# STM32WB55CGU6.net
KiCad netlist of a schematic drawn in Altium Designer
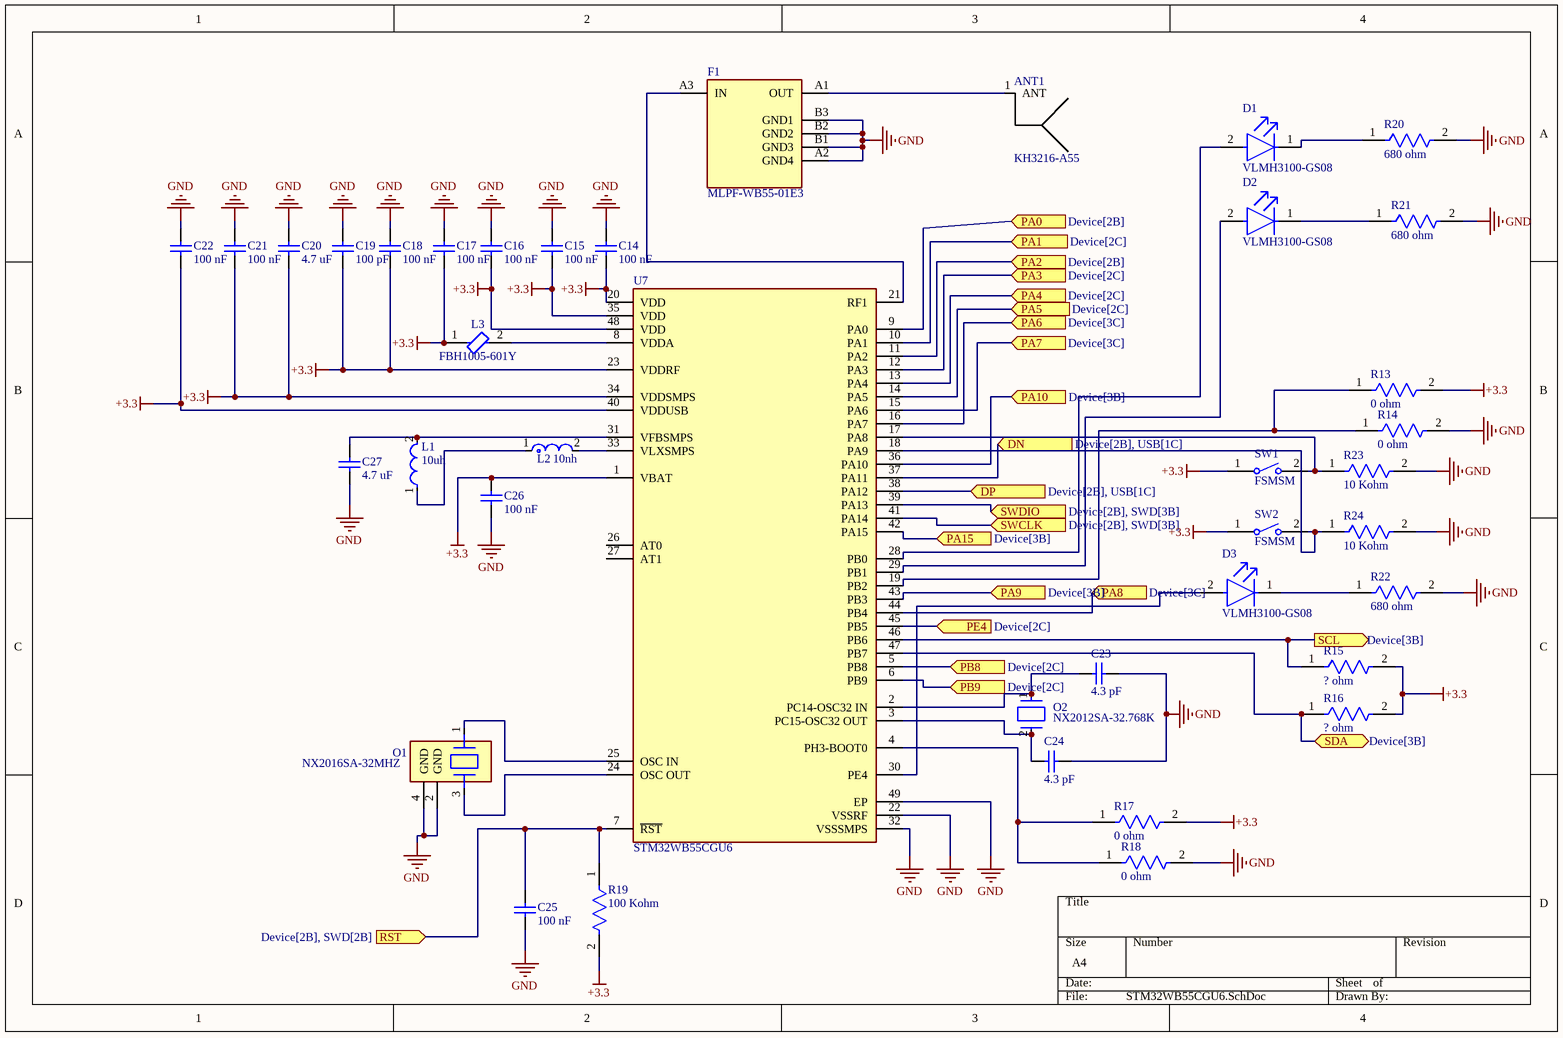
[diagram p0: STM32WB55CGU6.SchDoc]

(export (version "E")
  (design (tool "Eeschema 10.0.6"))
  (components
    (comp (ref "ANT1")
      (value "KH3216-A55")
      (footprint "KH3216-A55")
      (libsource (lib "ANT") (part "KH3216-A55"))
    )
    (comp (ref "C14")
      (value "100 nF")
      (footprint "CAPC1005X55X25NL05T10")
      (fields (field (name "MANUFACTURER") "Murata") (field (name "PART NUMBER") "GRM155F50J684ZE01D"))
      (libsource (lib "Altium Content Vault") (part "CAP"))
    )
    (comp (ref "C15")
      (value "100 nF")
      (footprint "CAPC1005X55X25NL05T10")
      (fields (field (name "MANUFACTURER") "Murata") (field (name "PART NUMBER") "GRM155F50J684ZE01D"))
      (libsource (lib "Altium Content Vault") (part "CAP"))
    )
    (comp (ref "C16")
      (value "100 nF")
      (footprint "CAPC1005X55X25NL05T10")
      (fields (field (name "MANUFACTURER") "Murata") (field (name "PART NUMBER") "GRM155F50J684ZE01D"))
      (libsource (lib "Altium Content Vault") (part "CAP"))
    )
    (comp (ref "C17")
      (value "100 nF")
      (footprint "CAPC1005X55X25NL05T10")
      (fields (field (name "MANUFACTURER") "Murata") (field (name "PART NUMBER") "GRM155F50J684ZE01D"))
      (libsource (lib "Altium Content Vault") (part "CAP"))
    )
    (comp (ref "C18")
      (value "100 nF")
      (footprint "CAPC1005X55X25NL05T10")
      (fields (field (name "MANUFACTURER") "Murata") (field (name "PART NUMBER") "GRM155F50J684ZE01D"))
      (libsource (lib "Altium Content Vault") (part "CAP"))
    )
    (comp (ref "C19")
      (value "100 pF")
      (footprint "CAPC1005X55X25NL05T10")
      (fields (field (name "MANUFACTURER") "Murata") (field (name "PART NUMBER") "GRM155F50J684ZE01D"))
      (libsource (lib "Altium Content Vault") (part "CAP"))
    )
    (comp (ref "C20")
      (value "4.7 uF")
      (footprint "CAPC1005X55X25NL05T10")
      (fields (field (name "MANUFACTURER") "Murata") (field (name "PART NUMBER") "GRM155F50J684ZE01D"))
      (libsource (lib "Altium Content Vault") (part "CAP"))
    )
    (comp (ref "C21")
      (value "100 nF")
      (footprint "CAPC1005X55X25NL05T10")
      (fields (field (name "MANUFACTURER") "Murata") (field (name "PART NUMBER") "GRM155F50J684ZE01D"))
      (libsource (lib "Altium Content Vault") (part "CAP"))
    )
    (comp (ref "C22")
      (value "100 nF")
      (footprint "CAPC1005X55X25NL05T10")
      (fields (field (name "MANUFACTURER") "Murata") (field (name "PART NUMBER") "GRM155F50J684ZE01D"))
      (libsource (lib "Altium Content Vault") (part "CAP"))
    )
    (comp (ref "C23")
      (value "4.3 pF")
      (footprint "CAPC1005X55X25NL05T10")
      (fields (field (name "MANUFACTURER") "Murata") (field (name "PART NUMBER") "GRM155F50J684ZE01D"))
      (libsource (lib "Altium Content Vault") (part "CAP"))
    )
    (comp (ref "C24")
      (value "4.3 pF")
      (footprint "CAPC1005X55X25NL05T10")
      (fields (field (name "MANUFACTURER") "Murata") (field (name "PART NUMBER") "GRM155F50J684ZE01D"))
      (libsource (lib "Altium Content Vault") (part "CAP"))
    )
    (comp (ref "C25")
      (value "100 nF")
      (footprint "CAPC1005X55X25NL05T10")
      (fields (field (name "MANUFACTURER") "Murata") (field (name "PART NUMBER") "GRM155F50J684ZE01D"))
      (libsource (lib "Altium Content Vault") (part "CAP"))
    )
    (comp (ref "C26")
      (value "100 nF")
      (footprint "CAPC1005X55X25NL05T10")
      (fields (field (name "MANUFACTURER") "Murata") (field (name "PART NUMBER") "GRM155F50J684ZE01D"))
      (libsource (lib "Altium Content Vault") (part "CAP"))
    )
    (comp (ref "C27")
      (value "4.7 uF")
      (footprint "CAPC1005X55X25NL05T10")
      (fields (field (name "MANUFACTURER") "Murata") (field (name "PART NUMBER") "GRM155F50J684ZE01D"))
      (libsource (lib "Altium Content Vault") (part "CAP"))
    )
    (comp (ref "D1")
      (value "VLMH3100-GS08")
      (footprint "FP-6_541-5067_01-4-MFG")
      (description "LED AMBER CLEAR 2PLCC SMD")
      (fields
        (field (name "MANUFACTURER") "Vishay")
        (field (name "OCTOPART") "https://octopart.com/vlmh3100-gs08-vishay-10477172")
      )
      (libsource (lib "Altium Content Vault") (part "f19a1b30ec2e0e83542a893ae8c56fc"))
    )
    (comp (ref "D2")
      (value "VLMH3100-GS08")
      (footprint "FP-6_541-5067_01-4-MFG")
      (description "LED AMBER CLEAR 2PLCC SMD")
      (fields
        (field (name "MANUFACTURER") "Vishay")
        (field (name "OCTOPART") "https://octopart.com/vlmh3100-gs08-vishay-10477172")
      )
      (libsource (lib "Altium Content Vault") (part "f19a1b30ec2e0e83542a893ae8c56fc"))
    )
    (comp (ref "D3")
      (value "VLMH3100-GS08")
      (footprint "FP-6_541-5067_01-4-MFG")
      (description "LED AMBER CLEAR 2PLCC SMD")
      (fields
        (field (name "MANUFACTURER") "Vishay")
        (field (name "OCTOPART") "https://octopart.com/vlmh3100-gs08-vishay-10477172")
      )
      (libsource (lib "Altium Content Vault") (part "f19a1b30ec2e0e83542a893ae8c56fc"))
    )
    (comp (ref "F1")
      (value "MLPF-WB55-01E3")
      (footprint "FP-MLPF-WB55-01E3-MFG")
      (description "RF FILTER LOW PASS 2.45GHZ 6SMD")
      (libsource (lib "Altium Content Vault") (part "51e28da9fe7b2e4e5e03ac85244eada"))
    )
    (comp (ref "L1")
      (value "10uh")
      (footprint "FP-LQM21FN_70-MFG")
      (description "FIXED IND 10UH 100MA 780MOHM SMD")
      (fields (field (name "TOLERANCE") "20%"))
      (libsource (lib "Altium Content Vault") (part "725321dda6339637d4d059423bc1c3c"))
    )
    (comp (ref "L2")
      (value "10nh")
      (footprint "FP-LQG15WH_02-MFG")
      (description "Multilayer type Inductor for Automotive 10nH ±5% 0.19Ω 500mA 0402")
      (fields (field (name "TOLERANCE") "5%"))
      (libsource (lib "Altium Content Vault") (part "4cc4b267dca4c8e51f7102f422741d8"))
    )
    (comp (ref "L3")
      (value "FBH1005-601Y")
      (footprint "FP-BLM15-0_05-MFG")
      (description "Chip Ferrite Bead, 0402, 600Ω @ 100MHz, 0.52Ω, 25%, 300mA")
      (fields (field (name "TOLERANCE") "25%"))
      (libsource (lib "Altium Content Vault") (part "5f30dd21d616792df468990f7003faa"))
    )
    (comp (ref "O1")
      (value "NX2016SA-32MHZ")
      (footprint "FP-NX2016SA-MFG")
      (description "CRYSTAL 32.0000MHZ 8PF SMD")
      (libsource (lib "Altium Content Vault") (part "0d11ad3ca7be055efd3b4f344707230"))
    )
    (comp (ref "O2")
      (value "NX2012SA-32.768K")
      (footprint "FP-NX2012SA-MFG")
      (description "CRYSTAL 32.7680KHZ 12.5PF SMD")
      (libsource (lib "Altium Content Vault") (part "c23a69dc6c9e2f18f2079038eb95dd1"))
    )
    (comp (ref "R13")
      (value "0 ohm")
      (footprint "FP-RC1005-IPC_C")
      (description "Res Thick Film 0402 1.87kΩ 1% 0.063W ±100ppm/°C Molded SMD T/R")
      (fields (field (name "TOLERANCE") "1%"))
      (libsource (lib "Altium Content Vault") (part "1029c3af85768c4190bb7ad29bc67b5"))
    )
    (comp (ref "R14")
      (value "0 ohm")
      (footprint "FP-RC1005-IPC_C")
      (description "Res Thick Film 0402 1.87kΩ 1% 0.063W ±100ppm/°C Molded SMD T/R")
      (fields (field (name "TOLERANCE") "1%"))
      (libsource (lib "Altium Content Vault") (part "1029c3af85768c4190bb7ad29bc67b5"))
    )
    (comp (ref "R15")
      (value "? ohm")
      (footprint "FP-RC1005-IPC_C")
      (description "Res Thick Film 0402 1.87kΩ 1% 0.063W ±100ppm/°C Molded SMD T/R")
      (fields (field (name "TOLERANCE") "1%"))
      (libsource (lib "Altium Content Vault") (part "1029c3af85768c4190bb7ad29bc67b5"))
    )
    (comp (ref "R16")
      (value "? ohm")
      (footprint "FP-RC1005-IPC_C")
      (description "Res Thick Film 0402 1.87kΩ 1% 0.063W ±100ppm/°C Molded SMD T/R")
      (fields (field (name "TOLERANCE") "1%"))
      (libsource (lib "Altium Content Vault") (part "1029c3af85768c4190bb7ad29bc67b5"))
    )
    (comp (ref "R17")
      (value "0 ohm")
      (footprint "FP-RC1005-IPC_C")
      (description "Res Thick Film 0402 1.87kΩ 1% 0.063W ±100ppm/°C Molded SMD T/R")
      (fields (field (name "TOLERANCE") "1%"))
      (libsource (lib "Altium Content Vault") (part "1029c3af85768c4190bb7ad29bc67b5"))
    )
    (comp (ref "R18")
      (value "0 ohm")
      (footprint "FP-RC1005-IPC_C")
      (description "Res Thick Film 0402 1.87kΩ 1% 0.063W ±100ppm/°C Molded SMD T/R")
      (fields (field (name "TOLERANCE") "1%"))
      (libsource (lib "Altium Content Vault") (part "1029c3af85768c4190bb7ad29bc67b5"))
    )
    (comp (ref "R19")
      (value "100 Kohm")
      (footprint "FP-RC1005-IPC_C")
      (description "Res Thick Film 0402 1.87kΩ 1% 0.063W ±100ppm/°C Molded SMD T/R")
      (fields (field (name "TOLERANCE") "1%"))
      (libsource (lib "Altium Content Vault") (part "1029c3af85768c4190bb7ad29bc67b5"))
    )
    (comp (ref "R20")
      (value "680 ohm")
      (footprint "FP-RC1005-IPC_C")
      (description "Res Thick Film 0402 1.87kΩ 1% 0.063W ±100ppm/°C Molded SMD T/R")
      (fields (field (name "TOLERANCE") "1%"))
      (libsource (lib "Altium Content Vault") (part "1029c3af85768c4190bb7ad29bc67b5"))
    )
    (comp (ref "R21")
      (value "680 ohm")
      (footprint "FP-RC1005-IPC_C")
      (description "Res Thick Film 0402 1.87kΩ 1% 0.063W ±100ppm/°C Molded SMD T/R")
      (fields (field (name "TOLERANCE") "1%"))
      (libsource (lib "Altium Content Vault") (part "1029c3af85768c4190bb7ad29bc67b5"))
    )
    (comp (ref "R22")
      (value "680 ohm")
      (footprint "FP-RC1005-IPC_C")
      (description "Res Thick Film 0402 1.87kΩ 1% 0.063W ±100ppm/°C Molded SMD T/R")
      (fields (field (name "TOLERANCE") "1%"))
      (libsource (lib "Altium Content Vault") (part "1029c3af85768c4190bb7ad29bc67b5"))
    )
    (comp (ref "R23")
      (value "10 Kohm")
      (footprint "FP-RC1005-IPC_C")
      (description "Res Thick Film 0402 1.87kΩ 1% 0.063W ±100ppm/°C Molded SMD T/R")
      (fields (field (name "TOLERANCE") "1%"))
      (libsource (lib "Altium Content Vault") (part "1029c3af85768c4190bb7ad29bc67b5"))
    )
    (comp (ref "R24")
      (value "10 Kohm")
      (footprint "FP-RC1005-IPC_C")
      (description "Res Thick Film 0402 1.87kΩ 1% 0.063W ±100ppm/°C Molded SMD T/R")
      (fields (field (name "TOLERANCE") "1%"))
      (libsource (lib "Altium Content Vault") (part "1029c3af85768c4190bb7ad29bc67b5"))
    )
    (comp (ref "SW1")
      (value "FSMSM")
      (footprint "TECO-FSMSM-2_V")
      (description "FSMSM Push Button Switch, 50 mA, -35 to 85 degC, 2-Pin SMD, RoHS, Bulk")
      (fields (field (name "MANUFACTURER") "TE Connectivity"))
      (libsource (lib "Altium Content Vault") (part "SW-SPST-2_C"))
    )
    (comp (ref "SW2")
      (value "FSMSM")
      (footprint "TECO-FSMSM-2_V")
      (description "FSMSM Push Button Switch, 50 mA, -35 to 85 degC, 2-Pin SMD, RoHS, Bulk")
      (fields (field (name "MANUFACTURER") "TE Connectivity"))
      (libsource (lib "Altium Content Vault") (part "SW-SPST-2_C"))
    )
    (comp (ref "U7")
      (value "STM32WB55CGU6")
      (footprint "FP-STM32WB55CGU6-MFG")
      (description "ULTRA-LOW-POWER DUAL CORE ARM CO")
      (fields
        (field (name "OCTOPART") "https://octopart.com/stm32wb55cgu6-stmicroelectronics-98750847")
        (field (name "MANUFACTURER") "STMicroelectronics")
      )
      (libsource (lib "Altium Content Vault") (part "9d9ca7f3567da95c474f3f549f05e68"))
    )
  )
  (nets
    (net (code "1") (name "+3.3") (class "Default")
      (node (ref "C14") (pin "1") (pinfunction "1_1") (pintype "passive"))
      (node (ref "C15") (pin "2") (pinfunction "2_2") (pintype "passive"))
      (node (ref "C16") (pin "1") (pinfunction "1_1") (pintype "passive"))
      (node (ref "C17") (pin "2") (pinfunction "2_2") (pintype "passive"))
      (node (ref "C18") (pin "1") (pinfunction "1_1") (pintype "passive"))
      (node (ref "C19") (pin "2") (pinfunction "2_2") (pintype "passive"))
      (node (ref "C20") (pin "2") (pinfunction "2_2") (pintype "passive"))
      (node (ref "C21") (pin "1") (pinfunction "1_1") (pintype "passive"))
      (node (ref "C22") (pin "2") (pinfunction "2_2") (pintype "passive"))
      (node (ref "C26") (pin "2") (pinfunction "2_2") (pintype "passive"))
      (node (ref "L3") (pin "1") (pinfunction "1_1") (pintype "passive"))
      (node (ref "R13") (pin "2") (pinfunction "2_2") (pintype "passive"))
      (node (ref "R15") (pin "2") (pinfunction "2_2") (pintype "passive"))
      (node (ref "R16") (pin "2") (pinfunction "2_2") (pintype "passive"))
      (node (ref "R17") (pin "2") (pinfunction "2_2") (pintype "passive"))
      (node (ref "R19") (pin "2") (pinfunction "2_2") (pintype "passive"))
      (node (ref "SW1") (pin "1") (pinfunction "1_1") (pintype "passive"))
      (node (ref "SW2") (pin "1") (pinfunction "1_1") (pintype "passive"))
      (node (ref "U7") (pin "1") (pinfunction "VBAT_1") (pintype "passive"))
      (node (ref "U7") (pin "20") (pinfunction "VDD_20") (pintype "passive"))
      (node (ref "U7") (pin "23") (pinfunction "VDDRF_23") (pintype "passive"))
      (node (ref "U7") (pin "34") (pinfunction "VDDSMPS_34") (pintype "passive"))
      (node (ref "U7") (pin "35") (pinfunction "VDD_35") (pintype "passive"))
      (node (ref "U7") (pin "40") (pinfunction "VDDUSB_40") (pintype "passive"))
      (node (ref "U7") (pin "48") (pinfunction "VDD_48") (pintype "passive"))
    )
    (net (code "2") (name "/DN") (class "Default")
      (node (ref "U7") (pin "37") (pinfunction "PA11_37") (pintype "passive"))
    )
    (net (code "3") (name "/DP") (class "Default")
      (node (ref "U7") (pin "38") (pinfunction "PA12_38") (pintype "passive"))
    )
    (net (code "4") (name "/PA0") (class "Default")
      (node (ref "U7") (pin "9") (pinfunction "PA0_9") (pintype "passive"))
    )
    (net (code "5") (name "/PA1") (class "Default")
      (node (ref "U7") (pin "10") (pinfunction "PA1_10") (pintype "passive"))
    )
    (net (code "6") (name "/PA2") (class "Default")
      (node (ref "U7") (pin "11") (pinfunction "PA2_11") (pintype "passive"))
    )
    (net (code "7") (name "/PA3") (class "Default")
      (node (ref "U7") (pin "12") (pinfunction "PA3_12") (pintype "passive"))
    )
    (net (code "8") (name "/PA4") (class "Default")
      (node (ref "U7") (pin "13") (pinfunction "PA4_13") (pintype "passive"))
    )
    (net (code "9") (name "/PA5") (class "Default")
      (node (ref "U7") (pin "14") (pinfunction "PA5_14") (pintype "passive"))
    )
    (net (code "10") (name "/PA6") (class "Default")
      (node (ref "U7") (pin "16") (pinfunction "PA7_16") (pintype "passive"))
    )
    (net (code "11") (name "/PA7") (class "Default")
      (node (ref "U7") (pin "15") (pinfunction "PA6_15") (pintype "passive"))
    )
    (net (code "12") (name "/PA8") (class "Default")
      (node (ref "U7") (pin "44") (pinfunction "PB4_44") (pintype "passive"))
    )
    (net (code "13") (name "/PA9") (class "Default")
      (node (ref "U7") (pin "43") (pinfunction "PB3_43") (pintype "passive"))
    )
    (net (code "14") (name "/PA10") (class "Default")
      (node (ref "U7") (pin "36") (pinfunction "PA10_36") (pintype "passive"))
    )
    (net (code "15") (name "/PA15") (class "Default")
      (node (ref "U7") (pin "42") (pinfunction "PA15_42") (pintype "passive"))
    )
    (net (code "16") (name "/PB8") (class "Default")
      (node (ref "U7") (pin "5") (pinfunction "PB8_5") (pintype "passive"))
    )
    (net (code "17") (name "/PB9") (class "Default")
      (node (ref "U7") (pin "6") (pinfunction "PB9_6") (pintype "passive"))
    )
    (net (code "18") (name "/PE4") (class "Default")
      (node (ref "U7") (pin "45") (pinfunction "PB5_45") (pintype "passive"))
    )
    (net (code "19") (name "/RST") (class "Default")
      (node (ref "C25") (pin "2") (pinfunction "2_2") (pintype "passive"))
      (node (ref "R19") (pin "1") (pinfunction "1_1") (pintype "passive"))
      (node (ref "U7") (pin "7") (pinfunction "~{RST}_7") (pintype "passive"))
    )
    (net (code "20") (name "/SCL") (class "Default")
      (node (ref "R15") (pin "1") (pinfunction "1_1") (pintype "passive"))
      (node (ref "U7") (pin "46") (pinfunction "PB6_46") (pintype "passive"))
    )
    (net (code "21") (name "/SDA") (class "Default")
      (node (ref "R16") (pin "1") (pinfunction "1_1") (pintype "passive"))
      (node (ref "U7") (pin "47") (pinfunction "PB7_47") (pintype "passive"))
    )
    (net (code "22") (name "/SWCLK") (class "Default")
      (node (ref "U7") (pin "41") (pinfunction "PA14_41") (pintype "passive"))
    )
    (net (code "23") (name "/SWDIO") (class "Default")
      (node (ref "U7") (pin "39") (pinfunction "PA13_39") (pintype "passive"))
    )
    (net (code "24") (name "GND") (class "Default")
      (node (ref "C14") (pin "2") (pinfunction "2_2") (pintype "passive"))
      (node (ref "C15") (pin "1") (pinfunction "1_1") (pintype "passive"))
      (node (ref "C16") (pin "2") (pinfunction "2_2") (pintype "passive"))
      (node (ref "C17") (pin "1") (pinfunction "1_1") (pintype "passive"))
      (node (ref "C18") (pin "2") (pinfunction "2_2") (pintype "passive"))
      (node (ref "C19") (pin "1") (pinfunction "1_1") (pintype "passive"))
      (node (ref "C20") (pin "1") (pinfunction "1_1") (pintype "passive"))
      (node (ref "C21") (pin "2") (pinfunction "2_2") (pintype "passive"))
      (node (ref "C22") (pin "1") (pinfunction "1_1") (pintype "passive"))
      (node (ref "C23") (pin "2") (pinfunction "2_2") (pintype "passive"))
      (node (ref "C24") (pin "1") (pinfunction "1_1") (pintype "passive"))
      (node (ref "C25") (pin "1") (pinfunction "1_1") (pintype "passive"))
      (node (ref "C26") (pin "1") (pinfunction "1_1") (pintype "passive"))
      (node (ref "C27") (pin "2") (pinfunction "2_2") (pintype "passive"))
      (node (ref "F1") (pin "A2") (pinfunction "GND4_A2") (pintype "power_in"))
      (node (ref "F1") (pin "B1") (pinfunction "GND3_B1") (pintype "power_in"))
      (node (ref "F1") (pin "B2") (pinfunction "GND2_B2") (pintype "power_in"))
      (node (ref "F1") (pin "B3") (pinfunction "GND1_B3") (pintype "power_in"))
      (node (ref "O1") (pin "2") (pinfunction "GND_2") (pintype "power_in"))
      (node (ref "O1") (pin "4") (pinfunction "GND_4") (pintype "power_in"))
      (node (ref "R14") (pin "2") (pinfunction "2_2") (pintype "passive"))
      (node (ref "R18") (pin "2") (pinfunction "2_2") (pintype "passive"))
      (node (ref "R20") (pin "2") (pinfunction "2_2") (pintype "passive"))
      (node (ref "R21") (pin "2") (pinfunction "2_2") (pintype "passive"))
      (node (ref "R22") (pin "2") (pinfunction "2_2") (pintype "passive"))
      (node (ref "R23") (pin "2") (pinfunction "2_2") (pintype "passive"))
      (node (ref "R24") (pin "2") (pinfunction "2_2") (pintype "passive"))
      (node (ref "U7") (pin "22") (pinfunction "VSSRF_22") (pintype "passive"))
      (node (ref "U7") (pin "32") (pinfunction "VSSSMPS_32") (pintype "passive"))
      (node (ref "U7") (pin "49") (pinfunction "EP_49") (pintype "power_in"))
    )
    (net (code "25") (name "Net-(ANT1-ANT)") (class "Default")
      (node (ref "ANT1") (pin "1") (pinfunction "ANT_1") (pintype "passive"))
      (node (ref "F1") (pin "A1") (pinfunction "OUT_A1") (pintype "passive"))
    )
    (net (code "26") (name "Net-(D1-A)") (class "Default")
      (node (ref "D1") (pin "2") (pinfunction "A_2") (pintype "passive"))
      (node (ref "U7") (pin "28") (pinfunction "PB0_28") (pintype "passive"))
    )
    (net (code "27") (name "Net-(D1-C)") (class "Default")
      (node (ref "D1") (pin "1") (pinfunction "C_1") (pintype "passive"))
      (node (ref "R20") (pin "1") (pinfunction "1_1") (pintype "passive"))
    )
    (net (code "28") (name "Net-(D2-A)") (class "Default")
      (node (ref "D2") (pin "2") (pinfunction "A_2") (pintype "passive"))
      (node (ref "U7") (pin "29") (pinfunction "PB1_29") (pintype "passive"))
    )
    (net (code "29") (name "Net-(D2-C)") (class "Default")
      (node (ref "D2") (pin "1") (pinfunction "C_1") (pintype "passive"))
      (node (ref "R21") (pin "1") (pinfunction "1_1") (pintype "passive"))
    )
    (net (code "30") (name "Net-(D3-A)") (class "Default")
      (node (ref "D3") (pin "2") (pinfunction "A_2") (pintype "passive"))
      (node (ref "U7") (pin "30") (pinfunction "PE4_30") (pintype "passive"))
    )
    (net (code "31") (name "Net-(D3-C)") (class "Default")
      (node (ref "D3") (pin "1") (pinfunction "C_1") (pintype "passive"))
      (node (ref "R22") (pin "1") (pinfunction "1_1") (pintype "passive"))
    )
    (net (code "32") (name "Net-(F1-IN)") (class "Default")
      (node (ref "F1") (pin "A3") (pinfunction "IN_A3") (pintype "power_in"))
      (node (ref "U7") (pin "21") (pinfunction "RF1_21") (pintype "passive"))
    )
    (net (code "33") (name "Net-(L1-Pad1)") (class "Default")
      (node (ref "L1") (pin "1") (pinfunction "1_1") (pintype "passive"))
      (node (ref "L2") (pin "1") (pinfunction "1_1") (pintype "passive"))
    )
    (net (code "34") (name "Net-(U7-OSC_IN)") (class "Default")
      (node (ref "O1") (pin "1") (pinfunction "1_1") (pintype "passive"))
      (node (ref "U7") (pin "25") (pinfunction "OSC_IN_25") (pintype "passive"))
    )
    (net (code "35") (name "Net-(U7-OSC_OUT)") (class "Default")
      (node (ref "O1") (pin "3") (pinfunction "3_3") (pintype "passive"))
      (node (ref "U7") (pin "24") (pinfunction "OSC_OUT_24") (pintype "passive"))
    )
    (net (code "36") (name "Net-(U7-PA8)") (class "Default")
      (node (ref "R23") (pin "1") (pinfunction "1_1") (pintype "passive"))
      (node (ref "SW1") (pin "2") (pinfunction "2_2") (pintype "passive"))
      (node (ref "U7") (pin "17") (pinfunction "PA8_17") (pintype "passive"))
    )
    (net (code "37") (name "Net-(U7-PA9)") (class "Default")
      (node (ref "R24") (pin "1") (pinfunction "1_1") (pintype "passive"))
      (node (ref "SW2") (pin "2") (pinfunction "2_2") (pintype "passive"))
      (node (ref "U7") (pin "18") (pinfunction "PA9_18") (pintype "passive"))
    )
    (net (code "38") (name "Net-(U7-PB2)") (class "Default")
      (node (ref "R13") (pin "1") (pinfunction "1_1") (pintype "passive"))
      (node (ref "R14") (pin "1") (pinfunction "1_1") (pintype "passive"))
      (node (ref "U7") (pin "19") (pinfunction "PB2_19") (pintype "passive"))
    )
    (net (code "39") (name "Net-(U7-PC14-OSC32_IN)") (class "Default")
      (node (ref "C23") (pin "1") (pinfunction "1_1") (pintype "passive"))
      (node (ref "O2") (pin "1") (pinfunction "1_1") (pintype "passive"))
      (node (ref "U7") (pin "2") (pinfunction "PC14-OSC32_IN_2") (pintype "passive"))
    )
    (net (code "40") (name "Net-(U7-PC15-OSC32_OUT)") (class "Default")
      (node (ref "C24") (pin "2") (pinfunction "2_2") (pintype "passive"))
      (node (ref "O2") (pin "2") (pinfunction "2_2") (pintype "passive"))
      (node (ref "U7") (pin "3") (pinfunction "PC15-OSC32_OUT_3") (pintype "passive"))
    )
    (net (code "41") (name "Net-(U7-PH3-BOOT0)") (class "Default")
      (node (ref "R17") (pin "1") (pinfunction "1_1") (pintype "passive"))
      (node (ref "R18") (pin "1") (pinfunction "1_1") (pintype "passive"))
      (node (ref "U7") (pin "4") (pinfunction "PH3-BOOT0_4") (pintype "passive"))
    )
    (net (code "42") (name "Net-(U7-VDDA)") (class "Default")
      (node (ref "L3") (pin "2") (pinfunction "2_2") (pintype "passive"))
      (node (ref "U7") (pin "8") (pinfunction "VDDA_8") (pintype "passive"))
    )
    (net (code "43") (name "Net-(U7-VFBSMPS)") (class "Default")
      (node (ref "C27") (pin "1") (pinfunction "1_1") (pintype "passive"))
      (node (ref "L1") (pin "2") (pinfunction "2_2") (pintype "passive"))
      (node (ref "U7") (pin "31") (pinfunction "VFBSMPS_31") (pintype "passive"))
    )
    (net (code "44") (name "Net-(U7-VLXSMPS)") (class "Default")
      (node (ref "L2") (pin "2") (pinfunction "2_2") (pintype "passive"))
      (node (ref "U7") (pin "33") (pinfunction "VLXSMPS_33") (pintype "passive"))
    )
    (net (code "45") (name "unconnected-(U7-AT0-Pad26)") (class "Default")
      (node (ref "U7") (pin "26") (pinfunction "AT0_26") (pintype "passive"))
    )
    (net (code "46") (name "unconnected-(U7-AT1-Pad27)") (class "Default")
      (node (ref "U7") (pin "27") (pinfunction "AT1_27") (pintype "passive"))
    )
  )
)
